# SK3000v3_-_FINAL_SMD.net
KiCad netlist of a schematic drawn in EAGLE
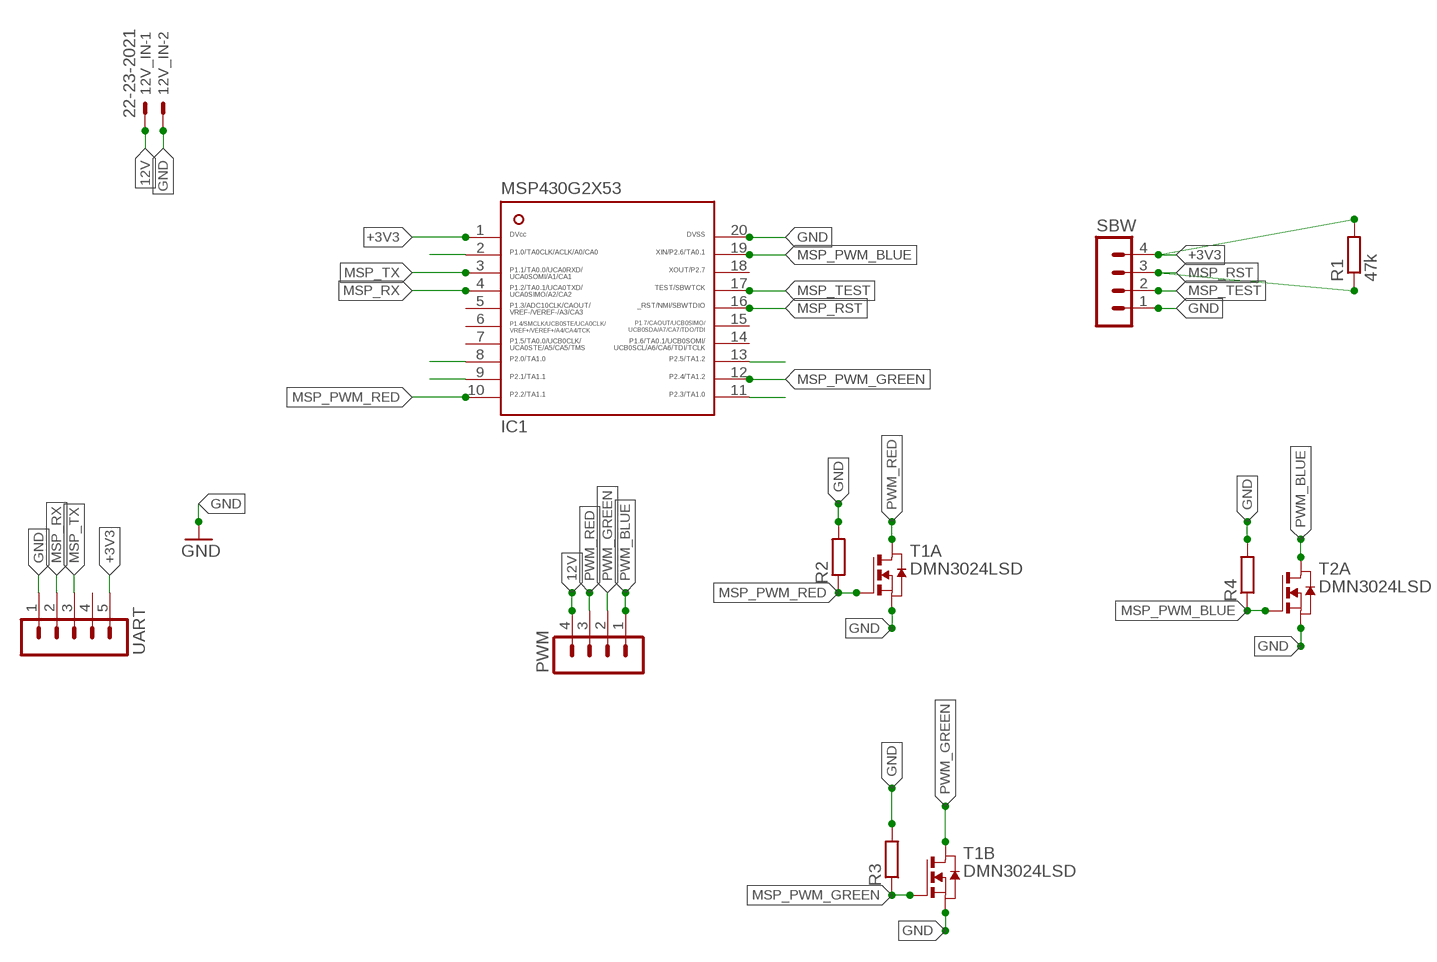
[diagram p0: schematic, sheet 1]

(export (version "E")
  (design (tool "Eeschema 10.0.6"))
  (components
    (comp (ref "12V_IN")
      (value "22-23-2021")
      (footprint "eagle-import:22-23-2021")
      (fields (field (name "MF") "MOLEX"))
      (libsource (lib "eagle-import") (part "22-23-2021"))
    )
    (comp (ref "IC1")
      (value "MSP430G2553")
      (footprint "eagle-import:PW20")
      (libsource (lib "eagle-import") (part "MSP430G2X53-20PW20"))
    )
    (comp (ref "PWM")
      (value "MA04-1")
      (footprint "eagle-import:MA04-1")
      (libsource (lib "eagle-import") (part "MA04-1"))
    )
    (comp (ref "R1")
      (value "47k")
      (footprint "eagle-import:R0603")
      (libsource (lib "eagle-import") (part "R-EU_R0603"))
    )
    (comp (ref "R2")
      (value "R-EU_R0603")
      (footprint "eagle-import:R0603")
      (libsource (lib "eagle-import") (part "R-EU_R0603"))
    )
    (comp (ref "R3")
      (value "R-EU_R0603")
      (footprint "eagle-import:R0603")
      (libsource (lib "eagle-import") (part "R-EU_R0603"))
    )
    (comp (ref "R4")
      (value "R-EU_R0603")
      (footprint "eagle-import:R0603")
      (libsource (lib "eagle-import") (part "R-EU_R0603"))
    )
    (comp (ref "SBW")
      (value "MA04-1")
      (footprint "eagle-import:MA04-1")
      (libsource (lib "eagle-import") (part "MA04-1"))
    )
    (comp (ref "T1")
      (value "DMN3024LSD")
      (footprint "eagle-import:SO8")
      (libsource (lib "eagle-import") (part "DMN3024LSD"))
    )
    (comp (ref "T2")
      (value "DMN3024LSD")
      (footprint "eagle-import:SO8")
      (libsource (lib "eagle-import") (part "DMN3024LSD"))
    )
    (comp (ref "UART")
      (value "MA05-1")
      (footprint "eagle-import:MA05-1")
      (libsource (lib "eagle-import") (part "MA05-1"))
    )
  )
  (nets
    (net (code "1") (name "+3V3") (class "Default")
      (node (ref "IC1") (pin "1") (pinfunction "1_1") (pintype "bidirectional"))
      (node (ref "R1") (pin "2") (pinfunction "2_2") (pintype "passive"))
      (node (ref "SBW") (pin "4") (pinfunction "4_4") (pintype "passive"))
      (node (ref "UART") (pin "5") (pinfunction "5_5") (pintype "passive"))
    )
    (net (code "2") (name "12V") (class "Default")
      (node (ref "12V_IN") (pin "1") (pinfunction "S_1") (pintype "passive"))
      (node (ref "PWM") (pin "4") (pinfunction "4_4") (pintype "passive"))
    )
    (net (code "3") (name "GND") (class "Default")
      (node (ref "12V_IN") (pin "2") (pinfunction "S_2") (pintype "passive"))
      (node (ref "IC1") (pin "20") (pinfunction "20_20") (pintype "bidirectional"))
      (node (ref "R2") (pin "2") (pinfunction "2_2") (pintype "passive"))
      (node (ref "R3") (pin "2") (pinfunction "2_2") (pintype "passive"))
      (node (ref "R4") (pin "2") (pinfunction "2_2") (pintype "passive"))
      (node (ref "SBW") (pin "1") (pinfunction "1_1") (pintype "passive"))
      (node (ref "T1") (pin "1") (pinfunction "S_1") (pintype "passive"))
      (node (ref "T1") (pin "3") (pinfunction "S_3") (pintype "passive"))
      (node (ref "T2") (pin "1") (pinfunction "S_1") (pintype "passive"))
      (node (ref "UART") (pin "1") (pinfunction "1_1") (pintype "passive"))
    )
    (net (code "4") (name "MSP_PWM_BLUE") (class "Default")
      (node (ref "IC1") (pin "19") (pinfunction "19_19") (pintype "bidirectional"))
      (node (ref "R4") (pin "1") (pinfunction "1_1") (pintype "passive"))
      (node (ref "T2") (pin "2") (pinfunction "G_2") (pintype "passive"))
    )
    (net (code "5") (name "MSP_PWM_GREEN") (class "Default")
      (node (ref "IC1") (pin "12") (pinfunction "12_12") (pintype "bidirectional"))
      (node (ref "R3") (pin "1") (pinfunction "1_1") (pintype "passive"))
      (node (ref "T1") (pin "4") (pinfunction "G_4") (pintype "passive"))
    )
    (net (code "6") (name "MSP_PWM_RED") (class "Default")
      (node (ref "IC1") (pin "10") (pinfunction "10_10") (pintype "bidirectional"))
      (node (ref "R2") (pin "1") (pinfunction "1_1") (pintype "passive"))
      (node (ref "T1") (pin "2") (pinfunction "G_2") (pintype "passive"))
    )
    (net (code "7") (name "MSP_RST") (class "Default")
      (node (ref "IC1") (pin "16") (pinfunction "16_16") (pintype "bidirectional"))
      (node (ref "R1") (pin "1") (pinfunction "1_1") (pintype "passive"))
      (node (ref "SBW") (pin "3") (pinfunction "3_3") (pintype "passive"))
    )
    (net (code "8") (name "MSP_RX") (class "Default")
      (node (ref "IC1") (pin "4") (pinfunction "4_4") (pintype "bidirectional"))
      (node (ref "UART") (pin "2") (pinfunction "2_2") (pintype "passive"))
    )
    (net (code "9") (name "MSP_TEST") (class "Default")
      (node (ref "IC1") (pin "17") (pinfunction "17_17") (pintype "bidirectional"))
      (node (ref "SBW") (pin "2") (pinfunction "2_2") (pintype "passive"))
    )
    (net (code "10") (name "MSP_TX") (class "Default")
      (node (ref "IC1") (pin "3") (pinfunction "3_3") (pintype "bidirectional"))
      (node (ref "UART") (pin "3") (pinfunction "3_3") (pintype "passive"))
    )
    (net (code "11") (name "PWM_BLUE") (class "Default")
      (node (ref "PWM") (pin "1") (pinfunction "1_1") (pintype "passive"))
      (node (ref "T2") (pin "7") (pinfunction "D_7") (pintype "passive"))
      (node (ref "T2") (pin "8") (pinfunction "D_8") (pintype "passive"))
    )
    (net (code "12") (name "PWM_GREEN") (class "Default")
      (node (ref "PWM") (pin "2") (pinfunction "2_2") (pintype "passive"))
      (node (ref "T1") (pin "5") (pinfunction "D_5") (pintype "passive"))
      (node (ref "T1") (pin "6") (pinfunction "D_6") (pintype "passive"))
    )
    (net (code "13") (name "PWM_RED") (class "Default")
      (node (ref "PWM") (pin "3") (pinfunction "3_3") (pintype "passive"))
      (node (ref "T1") (pin "7") (pinfunction "D_7") (pintype "passive"))
      (node (ref "T1") (pin "8") (pinfunction "D_8") (pintype "passive"))
    )
    (net (code "14") (name "unconnected-(IC1-Pad2)") (class "Default")
      (node (ref "IC1") (pin "2") (pinfunction "2_2") (pintype "bidirectional"))
    )
    (net (code "15") (name "unconnected-(IC1-Pad5)") (class "Default")
      (node (ref "IC1") (pin "5") (pinfunction "5_5") (pintype "bidirectional"))
    )
    (net (code "16") (name "unconnected-(IC1-Pad6)") (class "Default")
      (node (ref "IC1") (pin "6") (pinfunction "6_6") (pintype "bidirectional"))
    )
    (net (code "17") (name "unconnected-(IC1-Pad7)") (class "Default")
      (node (ref "IC1") (pin "7") (pinfunction "7_7") (pintype "bidirectional"))
    )
    (net (code "18") (name "unconnected-(IC1-Pad8)") (class "Default")
      (node (ref "IC1") (pin "8") (pinfunction "8_8") (pintype "bidirectional"))
    )
    (net (code "19") (name "unconnected-(IC1-Pad9)") (class "Default")
      (node (ref "IC1") (pin "9") (pinfunction "9_9") (pintype "bidirectional"))
    )
    (net (code "20") (name "unconnected-(IC1-Pad11)") (class "Default")
      (node (ref "IC1") (pin "11") (pinfunction "11_11") (pintype "bidirectional"))
    )
    (net (code "21") (name "unconnected-(IC1-Pad13)") (class "Default")
      (node (ref "IC1") (pin "13") (pinfunction "13_13") (pintype "bidirectional"))
    )
    (net (code "22") (name "unconnected-(IC1-Pad14)") (class "Default")
      (node (ref "IC1") (pin "14") (pinfunction "14_14") (pintype "bidirectional"))
    )
    (net (code "23") (name "unconnected-(IC1-Pad15)") (class "Default")
      (node (ref "IC1") (pin "15") (pinfunction "15_15") (pintype "bidirectional"))
    )
    (net (code "24") (name "unconnected-(IC1-Pad18)") (class "Default")
      (node (ref "IC1") (pin "18") (pinfunction "18_18") (pintype "bidirectional"))
    )
    (net (code "25") (name "unconnected-(UART-Pad4)") (class "Default")
      (node (ref "UART") (pin "4") (pinfunction "4_4") (pintype "passive"))
    )
  )
)
